# zasilacz_symetryczny_schemat.net
KiCad netlist of a schematic drawn in Altium Designer
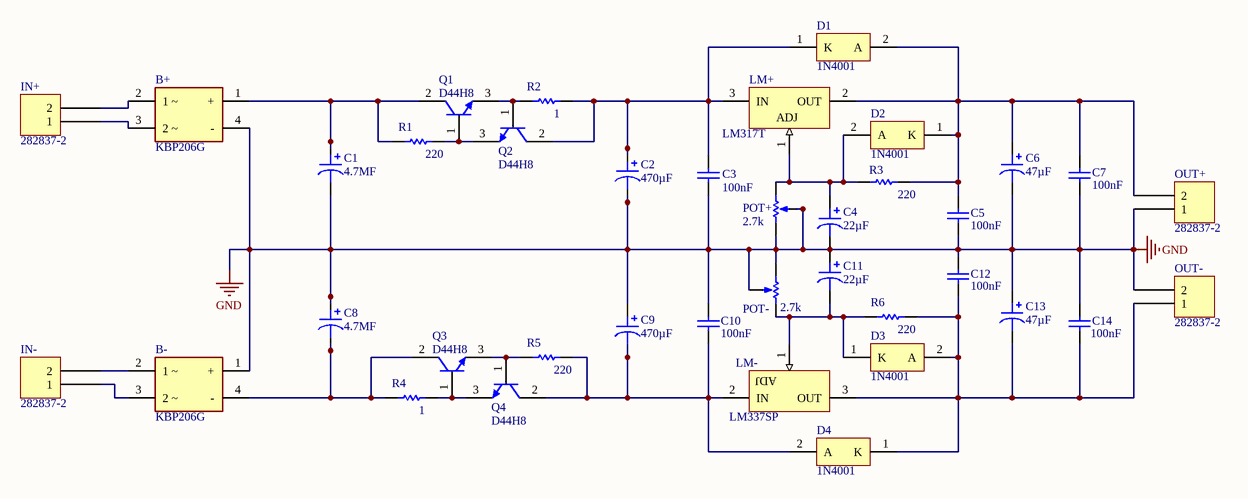
[diagram p0: zasilacz_symetryczny_schemat.SchDoc]

(export (version "E")
  (design (tool "Eeschema 10.0.6"))
  (components
    (comp (ref "B+")
      (value "KBP206G")
      (footprint "FP-KBP-MFG")
      (description "BRIDGE RECT 1PHASE 600V 2A KBP")
      (fields
        (field (name "OCTOPART") "https://octopart.com/kbp206g-diodes+inc.-330175")
        (field (name "MANUFACTURER") "Diodes Inc.")
      )
      (libsource (lib "Altium Content Vault") (part "3a1086ec435a8680de2aa37bc9d9ffa"))
    )
    (comp (ref "B-")
      (value "KBP206G")
      (footprint "FP-KBP-MFG")
      (description "BRIDGE RECT 1PHASE 600V 2A KBP")
      (fields
        (field (name "OCTOPART") "https://octopart.com/kbp206g-diodes+inc.-330175")
        (field (name "MANUFACTURER") "Diodes Inc.")
      )
      (libsource (lib "Altium Content Vault") (part "3a1086ec435a8680de2aa37bc9d9ffa"))
    )
    (comp (ref "C1")
      (value "4.7MF")
      (footprint "CAP TH ALUM ELEC D18.00mm S7.50mm H21.50mm")
      (description "ALUMINUM CAPACITOR")
      (fields
        (field (name "PART NUMBER") "EKYC250ELL472MM20S")
        (field (name "MANUFACTURER") "United Chemi-Con")
      )
      (libsource (lib "Celestial Altium Library - altium_library") (part "Polarised Capacitor"))
    )
    (comp (ref "C2")
      (value "470µF")
      (footprint "CAP TH ALUM ELEC D12.50mm S5.00mm H14.00mm")
      (description "CAP ALUM 470UF 20% 35V RADIAL")
      (fields (field (name "PART NUMBER") "URZ1V471MHD") (field (name "MANUFACTURER") "Nichicon"))
      (libsource (lib "Celestial Altium Library - altium_library") (part "Polarised Capacitor"))
    )
    (comp (ref "C3")
      (value "100nF")
      (footprint "RAD-0.3")
      (description "Capacitor")
      (fields (field (name "Comment") "Cap") (field (name "PUBLISHER") "Altium Limited"))
      (libsource (lib "Miscellaneous Devices") (part "Cap"))
    )
    (comp (ref "C4")
      (value "22µF")
      (footprint "CAP TH ALUM ELEC D5.00mm S2.00mm H11.00mm")
      (description "CAP ALUM 22UF 20% 35V RADIAL")
      (fields
        (field (name "PART NUMBER") "EEU-FC1V220")
        (field (name "MANUFACTURER") "Panasonic Electronic Components")
      )
      (libsource (lib "Celestial Altium Library - altium_library") (part "Polarised Capacitor"))
    )
    (comp (ref "C5")
      (value "100nF")
      (footprint "RAD-0.3")
      (description "Capacitor")
      (fields (field (name "Comment") "Cap") (field (name "PUBLISHER") "Altium Limited"))
      (libsource (lib "Miscellaneous Devices") (part "Cap"))
    )
    (comp (ref "C6")
      (value "47µF")
      (footprint "CAP TH ALUM ELEC D6.30mm S2.50mm H11.00mm")
      (description "CAP ALUM 47UF 20% 50V RADIAL")
      (fields (field (name "PART NUMBER") "UKW1H470MED") (field (name "MANUFACTURER") "Nichicon"))
      (libsource (lib "Celestial Altium Library - altium_library") (part "Polarised Capacitor"))
    )
    (comp (ref "C7")
      (value "100nF")
      (footprint "RAD-0.3")
      (description "Capacitor")
      (fields (field (name "Comment") "Cap") (field (name "PUBLISHER") "Altium Limited"))
      (libsource (lib "Miscellaneous Devices") (part "Cap"))
    )
    (comp (ref "C8")
      (value "4.7MF")
      (footprint "CAP TH ALUM ELEC D18.00mm S7.50mm H21.50mm")
      (description "ALUMINUM CAPACITOR")
      (fields
        (field (name "PART NUMBER") "EKYC250ELL472MM20S")
        (field (name "MANUFACTURER") "United Chemi-Con")
      )
      (libsource (lib "Celestial Altium Library - altium_library") (part "Polarised Capacitor"))
    )
    (comp (ref "C9")
      (value "470µF")
      (footprint "CAP TH ALUM ELEC D12.50mm S5.00mm H14.00mm")
      (description "CAP ALUM 470UF 20% 35V RADIAL")
      (fields (field (name "PART NUMBER") "URZ1V471MHD") (field (name "MANUFACTURER") "Nichicon"))
      (libsource (lib "Celestial Altium Library - altium_library") (part "Polarised Capacitor"))
    )
    (comp (ref "C10")
      (value "100nF")
      (footprint "RAD-0.3")
      (description "Capacitor")
      (fields (field (name "Comment") "Cap") (field (name "PUBLISHER") "Altium Limited"))
      (libsource (lib "Miscellaneous Devices") (part "Cap"))
    )
    (comp (ref "C11")
      (value "22µF")
      (footprint "CAP TH ALUM ELEC D5.00mm S2.00mm H11.00mm")
      (description "CAP ALUM 22UF 20% 35V RADIAL")
      (fields
        (field (name "PART NUMBER") "EEU-FC1V220")
        (field (name "MANUFACTURER") "Panasonic Electronic Components")
      )
      (libsource (lib "Celestial Altium Library - altium_library") (part "Polarised Capacitor"))
    )
    (comp (ref "C12")
      (value "100nF")
      (footprint "RAD-0.3")
      (description "Capacitor")
      (fields (field (name "Comment") "Cap") (field (name "PUBLISHER") "Altium Limited"))
      (libsource (lib "Miscellaneous Devices") (part "Cap"))
    )
    (comp (ref "C13")
      (value "47µF")
      (footprint "CAP TH ALUM ELEC D6.30mm S2.50mm H11.00mm")
      (description "CAP ALUM 47UF 20% 50V RADIAL")
      (fields (field (name "PART NUMBER") "UKW1H470MED") (field (name "MANUFACTURER") "Nichicon"))
      (libsource (lib "Celestial Altium Library - altium_library") (part "Polarised Capacitor"))
    )
    (comp (ref "C14")
      (value "100nF")
      (footprint "RAD-0.3")
      (description "Capacitor")
      (fields (field (name "Comment") "Cap") (field (name "PUBLISHER") "Altium Limited"))
      (libsource (lib "Miscellaneous Devices") (part "Cap"))
    )
    (comp (ref "D1")
      (value "1N4001")
      (footprint "ONSC-AXIAL_LEAD-2-59-10_P")
      (description "Standard Recovery Rectifier, 2-Pin Axial_Lead, Pb-Free, Bulk Bag")
      (fields (field (name "MANUFACTURER") "On Semiconductor"))
      (libsource (lib "") (part "ONSC-D-K1A2-2_A_1"))
    )
    (comp (ref "D2")
      (value "1N4001")
      (footprint "ONSC-AXIAL_LEAD-2-59-10_P")
      (description "Standard Recovery Rectifier, 2-Pin Axial_Lead, Pb-Free, Bulk Bag")
      (fields (field (name "MANUFACTURER") "On Semiconductor"))
      (libsource (lib "Altium Content Vault") (part "ONSC-D-K1A2-2_A"))
    )
    (comp (ref "D3")
      (value "1N4001")
      (footprint "ONSC-AXIAL_LEAD-2-59-10_P")
      (description "Standard Recovery Rectifier, 2-Pin Axial_Lead, Pb-Free, Bulk Bag")
      (fields (field (name "MANUFACTURER") "On Semiconductor"))
      (libsource (lib "") (part "ONSC-D-K1A2-2_A_1"))
    )
    (comp (ref "D4")
      (value "1N4001")
      (footprint "ONSC-AXIAL_LEAD-2-59-10_P")
      (description "Standard Recovery Rectifier, 2-Pin Axial_Lead, Pb-Free, Bulk Bag")
      (fields (field (name "MANUFACTURER") "On Semiconductor"))
      (libsource (lib "Altium Content Vault") (part "ONSC-D-K1A2-2_A"))
    )
    (comp (ref "IN+")
      (value "282837-2")
      (footprint "TE 282837-2")
      (description "TERM BLK 2P SIDE ENT 5.08MM PCB")
      (fields (field (name "MANUFACTURER") "TE Connectivity AMP Connectors") (field (name "VOLTAGE") "300 V"))
      (libsource (lib "Celestial Altium Library - altium_library") (part "2 Pin"))
    )
    (comp (ref "IN-")
      (value "282837-2")
      (footprint "TE 282837-2")
      (description "TERM BLK 2P SIDE ENT 5.08MM PCB")
      (fields (field (name "MANUFACTURER") "TE Connectivity AMP Connectors") (field (name "VOLTAGE") "300 V"))
      (libsource (lib "Celestial Altium Library - altium_library") (part "2 Pin"))
    )
    (comp (ref "LM+")
      (value "LM317T")
      (footprint "NDE0003A")
      (description "3-Terminal Adjustable Regulator, 3-pin TO-220")
      (fields (field (name "MANUFACTURER") "Texas Instruments"))
      (libsource (lib "Altium Content Vault") (part "PM-REG-LM1086ADJ-SIL3"))
    )
    (comp (ref "LM-")
      (value "LM337SP")
      (footprint "TO220")
      (description "Three-Terminal Negative Voltage Regulator, 3-Pin TO-220")
      (libsource (lib "Altium Content Vault") (part "PM-REG-117-CY3"))
    )
    (comp (ref "OUT+")
      (value "282837-2")
      (footprint "TE 282837-2")
      (description "TERM BLK 2P SIDE ENT 5.08MM PCB")
      (fields (field (name "MANUFACTURER") "TE Connectivity AMP Connectors") (field (name "VOLTAGE") "300 V"))
      (libsource (lib "") (part "2 Pin_1"))
    )
    (comp (ref "OUT-")
      (value "282837-2")
      (footprint "TE 282837-2")
      (description "TERM BLK 2P SIDE ENT 5.08MM PCB")
      (fields (field (name "MANUFACTURER") "TE Connectivity AMP Connectors") (field (name "VOLTAGE") "300 V"))
      (libsource (lib "") (part "2 Pin_1"))
    )
    (comp (ref "POT+")
      (value "2.7k")
      (footprint "VR5")
      (description "Potentiometer")
      (fields (field (name "Comment") "RPot") (field (name "PUBLISHER") "Altium Limited"))
      (libsource (lib "Miscellaneous Devices") (part "RPot"))
    )
    (comp (ref "POT-")
      (value "2.7k")
      (footprint "VR5")
      (description "Potentiometer")
      (fields (field (name "Comment") "RPot") (field (name "PUBLISHER") "Altium Limited"))
      (libsource (lib "Miscellaneous Devices") (part "RPot"))
    )
    (comp (ref "Q1")
      (value "D44H8")
      (footprint "ONSC-TO-220-3-221A-09")
      (description "Complementary Silicon Power Transistor, 3-Pin TO-220, Tube")
      (fields (field (name "MANUFACTURER") "On Semiconductor"))
      (libsource (lib "Altium Content Vault") (part "ONSC-NPN-B1C2E3-3_C"))
    )
    (comp (ref "Q2")
      (value "D44H8")
      (footprint "ONSC-TO-220-3-221A-09")
      (description "Complementary Silicon Power Transistor, 3-Pin TO-220, Tube")
      (fields (field (name "MANUFACTURER") "On Semiconductor"))
      (libsource (lib "Altium Content Vault") (part "ONSC-NPN-B1C2E3-3_C"))
    )
    (comp (ref "Q3")
      (value "D44H8")
      (footprint "ONSC-TO-220-3-221A-09")
      (description "Complementary Silicon Power Transistor, 3-Pin TO-220, Tube")
      (fields (field (name "MANUFACTURER") "On Semiconductor"))
      (libsource (lib "Altium Content Vault") (part "ONSC-NPN-B1C2E3-3_C"))
    )
    (comp (ref "Q4")
      (value "D44H8")
      (footprint "ONSC-TO-220-3-221A-09")
      (description "Complementary Silicon Power Transistor, 3-Pin TO-220, Tube")
      (fields (field (name "MANUFACTURER") "On Semiconductor"))
      (libsource (lib "Altium Content Vault") (part "ONSC-NPN-B1C2E3-3_C"))
    )
    (comp (ref "R1")
      (value "220")
      (footprint "AXIAL-0.3")
      (description "Resistor")
      (fields (field (name "Comment") "Res1") (field (name "PUBLISHER") "Altium Limited"))
      (libsource (lib "Miscellaneous Devices") (part "Res1"))
    )
    (comp (ref "R2")
      (value "1")
      (footprint "AXIAL-0.3")
      (description "Resistor")
      (fields (field (name "Comment") "Res1") (field (name "PUBLISHER") "Altium Limited"))
      (libsource (lib "Miscellaneous Devices") (part "Res1"))
    )
    (comp (ref "R3")
      (value "220")
      (footprint "AXIAL-0.3")
      (description "Resistor")
      (fields (field (name "Comment") "Res1") (field (name "PUBLISHER") "Altium Limited"))
      (libsource (lib "Miscellaneous Devices") (part "Res1"))
    )
    (comp (ref "R4")
      (value "1")
      (footprint "AXIAL-0.3")
      (description "Resistor")
      (fields (field (name "Comment") "Res1") (field (name "PUBLISHER") "Altium Limited"))
      (libsource (lib "Miscellaneous Devices") (part "Res1"))
    )
    (comp (ref "R5")
      (value "220")
      (footprint "AXIAL-0.3")
      (description "Resistor")
      (fields (field (name "Comment") "Res1") (field (name "PUBLISHER") "Altium Limited"))
      (libsource (lib "Miscellaneous Devices") (part "Res1"))
    )
    (comp (ref "R6")
      (value "220")
      (footprint "AXIAL-0.3")
      (description "Resistor")
      (fields (field (name "Comment") "Res1") (field (name "PUBLISHER") "Altium Limited"))
      (libsource (lib "Miscellaneous Devices") (part "Res1"))
    )
  )
  (nets
    (net (code "1") (name "GND") (class "Default")
      (node (ref "B+") (pin "4") (pinfunction "-_4") (pintype "passive"))
      (node (ref "B-") (pin "1") (pinfunction "+_1") (pintype "passive"))
      (node (ref "C1") (pin "2") (pinfunction "2_2") (pintype "passive"))
      (node (ref "C10") (pin "2") (pinfunction "2_2") (pintype "passive"))
      (node (ref "C11") (pin "1") (pinfunction "1_1") (pintype "passive"))
      (node (ref "C12") (pin "2") (pinfunction "2_2") (pintype "passive"))
      (node (ref "C13") (pin "1") (pinfunction "1_1") (pintype "passive"))
      (node (ref "C14") (pin "2") (pinfunction "2_2") (pintype "passive"))
      (node (ref "C2") (pin "2") (pinfunction "2_2") (pintype "passive"))
      (node (ref "C3") (pin "1") (pinfunction "1_1") (pintype "passive"))
      (node (ref "C4") (pin "2") (pinfunction "2_2") (pintype "passive"))
      (node (ref "C5") (pin "1") (pinfunction "1_1") (pintype "passive"))
      (node (ref "C6") (pin "2") (pinfunction "2_2") (pintype "passive"))
      (node (ref "C7") (pin "1") (pinfunction "1_1") (pintype "passive"))
      (node (ref "C8") (pin "1") (pinfunction "1_1") (pintype "passive"))
      (node (ref "C9") (pin "1") (pinfunction "1_1") (pintype "passive"))
      (node (ref "OUT+") (pin "1") (pinfunction "1_1") (pintype "passive"))
      (node (ref "OUT-") (pin "2") (pinfunction "2_2") (pintype "passive"))
      (node (ref "POT+") (pin "1") (pinfunction "TOP_1") (pintype "passive"))
      (node (ref "POT+") (pin "3") (pinfunction "TAP_3") (pintype "passive"))
      (node (ref "POT-") (pin "1") (pinfunction "TOP_1") (pintype "passive"))
      (node (ref "POT-") (pin "3") (pinfunction "TAP_3") (pintype "passive"))
    )
    (net (code "2") (name "Net-(B+-+)") (class "Default")
      (node (ref "B+") (pin "1") (pinfunction "+_1") (pintype "passive"))
      (node (ref "C1") (pin "1") (pinfunction "1_1") (pintype "passive"))
      (node (ref "Q1") (pin "2") (pinfunction "C_2") (pintype "passive"))
      (node (ref "R1") (pin "1") (pinfunction "1_1") (pintype "passive"))
    )
    (net (code "3") (name "Net-(B+-1_~)") (class "Default")
      (node (ref "B+") (pin "2") (pinfunction "1_~_2") (pintype "passive"))
      (node (ref "IN+") (pin "2") (pinfunction "2_2") (pintype "passive"))
    )
    (net (code "4") (name "Net-(B+-2_~)") (class "Default")
      (node (ref "B+") (pin "3") (pinfunction "2_~_3") (pintype "passive"))
      (node (ref "IN+") (pin "1") (pinfunction "1_1") (pintype "passive"))
    )
    (net (code "5") (name "Net-(B---)") (class "Default")
      (node (ref "B-") (pin "4") (pinfunction "-_4") (pintype "passive"))
      (node (ref "C8") (pin "2") (pinfunction "2_2") (pintype "passive"))
      (node (ref "Q3") (pin "2") (pinfunction "C_2") (pintype "passive"))
      (node (ref "R4") (pin "1") (pinfunction "1_1") (pintype "passive"))
    )
    (net (code "6") (name "Net-(B--1_~)") (class "Default")
      (node (ref "B-") (pin "2") (pinfunction "1_~_2") (pintype "passive"))
      (node (ref "IN-") (pin "2") (pinfunction "2_2") (pintype "passive"))
    )
    (net (code "7") (name "Net-(B--2_~)") (class "Default")
      (node (ref "B-") (pin "3") (pinfunction "2_~_3") (pintype "passive"))
      (node (ref "IN-") (pin "1") (pinfunction "1_1") (pintype "passive"))
    )
    (net (code "8") (name "Net-(D1-A)") (class "Default")
      (node (ref "C5") (pin "2") (pinfunction "2_2") (pintype "passive"))
      (node (ref "C6") (pin "1") (pinfunction "1_1") (pintype "passive"))
      (node (ref "C7") (pin "2") (pinfunction "2_2") (pintype "passive"))
      (node (ref "D1") (pin "2") (pinfunction "A_2") (pintype "passive"))
      (node (ref "D2") (pin "1") (pinfunction "K_1") (pintype "passive"))
      (node (ref "LM+") (pin "2") (pinfunction "OUT_2") (pintype "power_in"))
      (node (ref "OUT+") (pin "2") (pinfunction "2_2") (pintype "passive"))
      (node (ref "R3") (pin "2") (pinfunction "2_2") (pintype "passive"))
    )
    (net (code "9") (name "Net-(D1-K)") (class "Default")
      (node (ref "C2") (pin "1") (pinfunction "1_1") (pintype "passive"))
      (node (ref "C3") (pin "2") (pinfunction "2_2") (pintype "passive"))
      (node (ref "D1") (pin "1") (pinfunction "K_1") (pintype "passive"))
      (node (ref "LM+") (pin "3") (pinfunction "IN_3") (pintype "power_in"))
      (node (ref "Q2") (pin "2") (pinfunction "C_2") (pintype "passive"))
      (node (ref "R2") (pin "2") (pinfunction "2_2") (pintype "passive"))
    )
    (net (code "10") (name "Net-(D2-A)") (class "Default")
      (node (ref "C4") (pin "1") (pinfunction "1_1") (pintype "passive"))
      (node (ref "D2") (pin "2") (pinfunction "A_2") (pintype "passive"))
      (node (ref "LM+") (pin "1") (pinfunction "ADJ_1") (pintype "input"))
      (node (ref "POT+") (pin "2") (pinfunction "BOT_2") (pintype "passive"))
      (node (ref "R3") (pin "1") (pinfunction "1_1") (pintype "passive"))
    )
    (net (code "11") (name "Net-(D3-A)") (class "Default")
      (node (ref "C12") (pin "1") (pinfunction "1_1") (pintype "passive"))
      (node (ref "C13") (pin "2") (pinfunction "2_2") (pintype "passive"))
      (node (ref "C14") (pin "1") (pinfunction "1_1") (pintype "passive"))
      (node (ref "D3") (pin "2") (pinfunction "A_2") (pintype "passive"))
      (node (ref "D4") (pin "1") (pinfunction "K_1") (pintype "passive"))
      (node (ref "LM-") (pin "3") (pinfunction "OUT_3") (pintype "power_in"))
      (node (ref "OUT-") (pin "1") (pinfunction "1_1") (pintype "passive"))
      (node (ref "R6") (pin "2") (pinfunction "2_2") (pintype "passive"))
    )
    (net (code "12") (name "Net-(D3-K)") (class "Default")
      (node (ref "C11") (pin "2") (pinfunction "2_2") (pintype "passive"))
      (node (ref "D3") (pin "1") (pinfunction "K_1") (pintype "passive"))
      (node (ref "LM-") (pin "1") (pinfunction "ADJ_1") (pintype "input"))
      (node (ref "POT-") (pin "2") (pinfunction "BOT_2") (pintype "passive"))
      (node (ref "R6") (pin "1") (pinfunction "1_1") (pintype "passive"))
    )
    (net (code "13") (name "Net-(D4-A)") (class "Default")
      (node (ref "C10") (pin "1") (pinfunction "1_1") (pintype "passive"))
      (node (ref "C9") (pin "2") (pinfunction "2_2") (pintype "passive"))
      (node (ref "D4") (pin "2") (pinfunction "A_2") (pintype "passive"))
      (node (ref "LM-") (pin "2") (pinfunction "IN_2") (pintype "power_in"))
      (node (ref "Q4") (pin "2") (pinfunction "C_2") (pintype "passive"))
      (node (ref "R5") (pin "2") (pinfunction "2_2") (pintype "passive"))
    )
    (net (code "14") (name "Net-(Q1-B)") (class "Default")
      (node (ref "Q1") (pin "1") (pinfunction "B_1") (pintype "passive"))
      (node (ref "Q2") (pin "3") (pinfunction "E_3") (pintype "passive"))
      (node (ref "R1") (pin "2") (pinfunction "2_2") (pintype "passive"))
    )
    (net (code "15") (name "Net-(Q1-E)") (class "Default")
      (node (ref "Q1") (pin "3") (pinfunction "E_3") (pintype "passive"))
      (node (ref "Q2") (pin "1") (pinfunction "B_1") (pintype "passive"))
      (node (ref "R2") (pin "1") (pinfunction "1_1") (pintype "passive"))
    )
    (net (code "16") (name "Net-(Q3-B)") (class "Default")
      (node (ref "Q3") (pin "1") (pinfunction "B_1") (pintype "passive"))
      (node (ref "Q4") (pin "3") (pinfunction "E_3") (pintype "passive"))
      (node (ref "R4") (pin "2") (pinfunction "2_2") (pintype "passive"))
    )
    (net (code "17") (name "Net-(Q3-E)") (class "Default")
      (node (ref "Q3") (pin "3") (pinfunction "E_3") (pintype "passive"))
      (node (ref "Q4") (pin "1") (pinfunction "B_1") (pintype "passive"))
      (node (ref "R5") (pin "1") (pinfunction "1_1") (pintype "passive"))
    )
  )
)
